# Moist_Detector.net
KiCad netlist of a schematic drawn in EAGLE
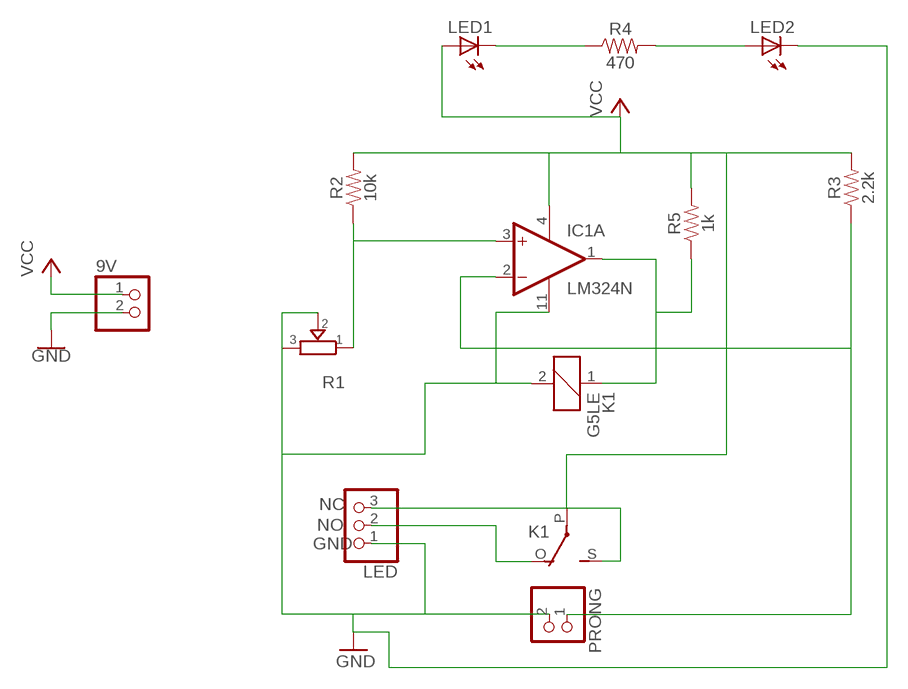
[diagram p0: schematic, sheet 1]

(export (version "E")
  (design (tool "Eeschema 10.0.6"))
  (components
    (comp (ref "9V")
      (value "PINHD-1X2")
      (footprint "eagle-import:1X02")
      (libsource (lib "eagle-import") (part "PINHD-1X2"))
    )
    (comp (ref "IC1")
      (value "LM324N")
      (footprint "eagle-import:DIL14")
      (libsource (lib "eagle-import") (part "LM324N"))
    )
    (comp (ref "K1")
      (value "G5LE")
      (footprint "eagle-import:G5LE")
      (libsource (lib "eagle-import") (part "G5LE"))
    )
    (comp (ref "LED")
      (value "PINHD-1X3")
      (footprint "eagle-import:1X03")
      (libsource (lib "eagle-import") (part "PINHD-1X3"))
    )
    (comp (ref "LED1")
      (value "LED-5MM")
      (footprint "eagle-import:LED-5MM")
      (libsource (lib "eagle-import") (part "LED-5MM"))
    )
    (comp (ref "LED2")
      (value "LED-5MM")
      (footprint "eagle-import:LED-5MM")
      (libsource (lib "eagle-import") (part "LED-5MM"))
    )
    (comp (ref "PRONG")
      (value "PINHD-1X2")
      (footprint "eagle-import:1X02")
      (libsource (lib "eagle-import") (part "PINHD-1X2"))
    )
    (comp (ref "R1")
      (value "TRIMMER-3306F")
      (footprint "eagle-import:TRIMMER_3306F")
      (libsource (lib "eagle-import") (part "TRIMMER-3306F"))
    )
    (comp (ref "R2")
      (value "10k")
      (footprint "eagle-import:AXIAL-0.3")
      (libsource (lib "eagle-import") (part "10KOHM-HORIZ-1/4W-5%"))
    )
    (comp (ref "R3")
      (value "2.2k")
      (footprint "eagle-import:AXIAL-0.3")
      (libsource (lib "eagle-import") (part "1KOHM-HORIZ-1/4W-5%"))
    )
    (comp (ref "R4")
      (value "470")
      (footprint "eagle-import:AXIAL-0.3")
      (libsource (lib "eagle-import") (part "1KOHM-HORIZ-1/4W-5%"))
    )
    (comp (ref "R5")
      (value "1k")
      (footprint "eagle-import:AXIAL-0.3")
      (libsource (lib "eagle-import") (part "10KOHM-HORIZ-1/4W-5%"))
    )
  )
  (nets
    (net (code "1") (name "GND") (class "Default")
      (node (ref "9V") (pin "2") (pinfunction "2_2") (pintype "passive"))
      (node (ref "IC1") (pin "11") (pinfunction "V-_11") (pintype "power_in"))
      (node (ref "K1") (pin "2") (pinfunction "2_2") (pintype "passive"))
      (node (ref "LED") (pin "1") (pinfunction "1_1") (pintype "passive"))
      (node (ref "LED2") (pin "K") (pinfunction "C_K") (pintype "passive"))
      (node (ref "PRONG") (pin "2") (pinfunction "2_2") (pintype "passive"))
      (node (ref "R1") (pin "2") (pinfunction "2_2") (pintype "passive"))
      (node (ref "R1") (pin "3") (pinfunction "3_3") (pintype "passive"))
    )
    (net (code "2") (name "Net-(IC1A-+IN)") (class "Default")
      (node (ref "IC1") (pin "3") (pinfunction "+IN_3") (pintype "input"))
      (node (ref "R1") (pin "1") (pinfunction "1_1") (pintype "passive"))
      (node (ref "R2") (pin "P$1") (pinfunction "1_P$1") (pintype "passive"))
    )
    (net (code "3") (name "Net-(IC1A--IN)") (class "Default")
      (node (ref "IC1") (pin "2") (pinfunction "-IN_2") (pintype "input"))
      (node (ref "PRONG") (pin "1") (pinfunction "1_1") (pintype "passive"))
      (node (ref "R3") (pin "P$1") (pinfunction "1_P$1") (pintype "passive"))
    )
    (net (code "4") (name "Net-(IC1A-OUT)") (class "Default")
      (node (ref "IC1") (pin "1") (pinfunction "OUT_1") (pintype "output"))
      (node (ref "K1") (pin "1") (pinfunction "1_1") (pintype "passive"))
      (node (ref "R5") (pin "P$1") (pinfunction "1_P$1") (pintype "passive"))
    )
    (net (code "5") (name "Net-(K1-PadO)") (class "Default")
      (node (ref "K1") (pin "O") (pinfunction "O_O") (pintype "passive"))
      (node (ref "LED") (pin "2") (pinfunction "2_2") (pintype "passive"))
    )
    (net (code "6") (name "Net-(K1-PadS)") (class "Default")
      (node (ref "K1") (pin "S") (pinfunction "S_S") (pintype "passive"))
      (node (ref "LED") (pin "3") (pinfunction "3_3") (pintype "passive"))
    )
    (net (code "7") (name "Net-(LED1-C)") (class "Default")
      (node (ref "LED1") (pin "K") (pinfunction "C_K") (pintype "passive"))
      (node (ref "R4") (pin "P$1") (pinfunction "1_P$1") (pintype "passive"))
    )
    (net (code "8") (name "Net-(R4-2)") (class "Default")
      (node (ref "LED2") (pin "A") (pinfunction "A_A") (pintype "passive"))
      (node (ref "R4") (pin "P$2") (pinfunction "2_P$2") (pintype "passive"))
    )
    (net (code "9") (name "VCC") (class "Default")
      (node (ref "9V") (pin "1") (pinfunction "1_1") (pintype "passive"))
      (node (ref "IC1") (pin "4") (pinfunction "V+_4") (pintype "power_in"))
      (node (ref "K1") (pin "P") (pinfunction "P_P") (pintype "passive"))
      (node (ref "LED1") (pin "A") (pinfunction "A_A") (pintype "passive"))
      (node (ref "R2") (pin "P$2") (pinfunction "2_P$2") (pintype "passive"))
      (node (ref "R3") (pin "P$2") (pinfunction "2_P$2") (pintype "passive"))
      (node (ref "R5") (pin "P$2") (pinfunction "2_P$2") (pintype "passive"))
    )
  )
)
